# G1Tech-MCP4725-PCB_v02.net
KiCad netlist of a schematic drawn in EAGLE
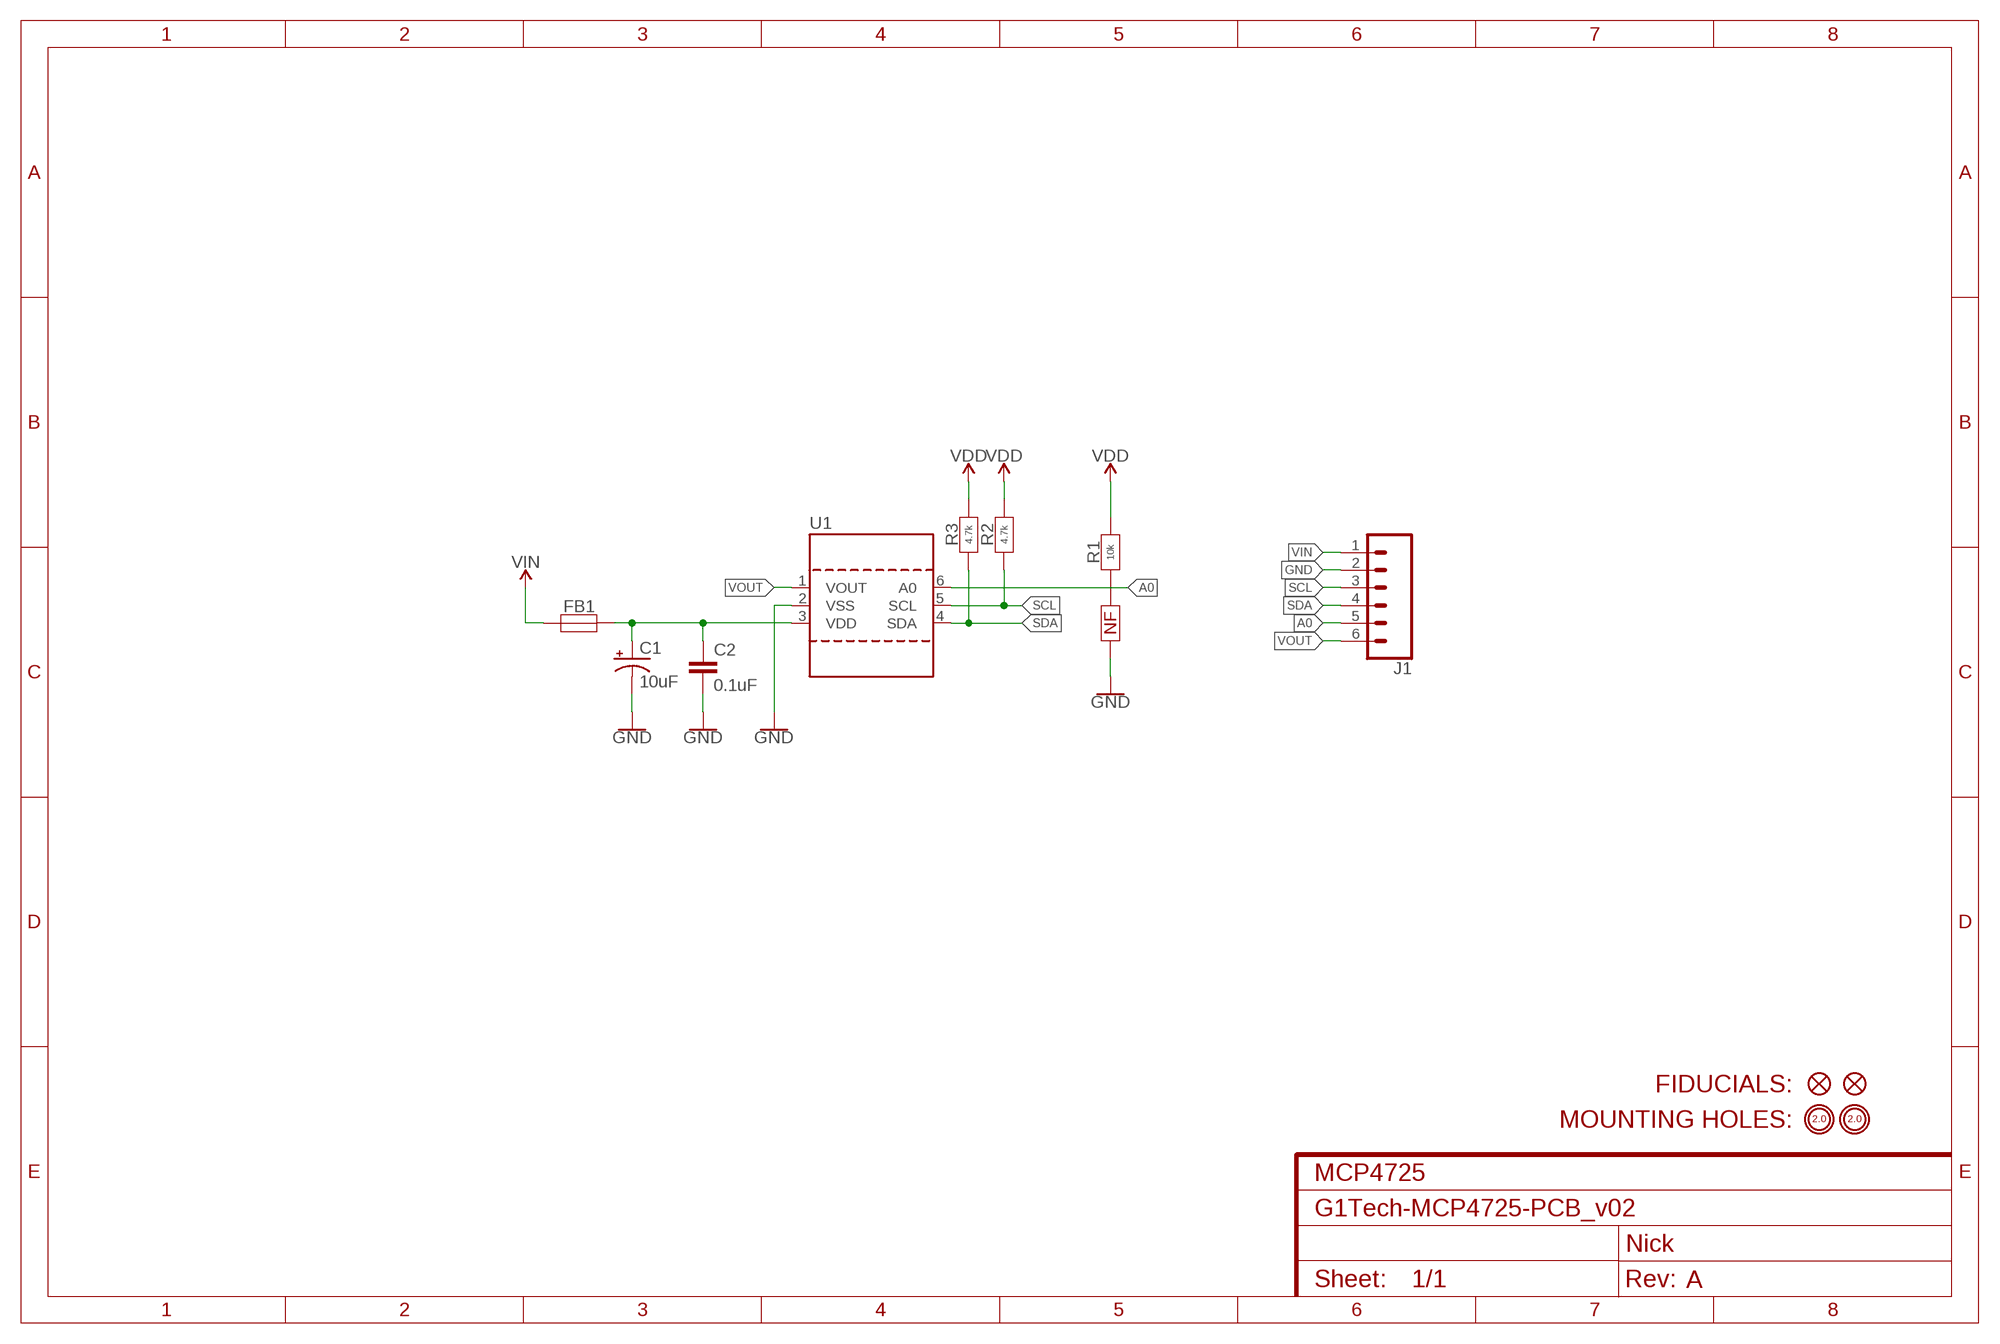
[diagram p0: schematic, sheet 1]

(export (version "E")
  (design (tool "Eeschema 10.0.6"))
  (components
    (comp (ref "C1")
      (value "10uF")
      (footprint "eagle-import:TYPE-A")
      (libsource (lib "eagle-import") (part "C-TYPE-A"))
    )
    (comp (ref "C2")
      (value "0.1uF")
      (footprint "eagle-import:C0603")
      (libsource (lib "eagle-import") (part "C0603"))
    )
    (comp (ref "FB1")
      (value "FERRITE-BEAD-0603")
      (footprint "eagle-import:FB-0603")
      (libsource (lib "eagle-import") (part "FERRITE-BEAD-0603"))
    )
    (comp (ref "FD1")
      (value "FIDUCIAL-1X2")
      (footprint "eagle-import:FIDUCIAL-1X2")
      (libsource (lib "eagle-import") (part "FIDUCIAL-1X2"))
    )
    (comp (ref "FD2")
      (value "FIDUCIAL-1X2")
      (footprint "eagle-import:FIDUCIAL-1X2")
      (libsource (lib "eagle-import") (part "FIDUCIAL-1X2"))
    )
    (comp (ref "H1")
      (value "MOUNTINGHOLE-PLATED-2.0")
      (footprint "eagle-import:MOUNTINGHOLE-PLATED-2.0")
      (libsource (lib "eagle-import") (part "MOUNTINGHOLE-PLATED-2.0"))
    )
    (comp (ref "H2")
      (value "MOUNTINGHOLE-PLATED-2.0")
      (footprint "eagle-import:MOUNTINGHOLE-PLATED-2.0")
      (libsource (lib "eagle-import") (part "MOUNTINGHOLE-PLATED-2.0"))
    )
    (comp (ref "J1")
      (value "CONN-1X6")
      (footprint "eagle-import:1X06_NO_SILK")
      (libsource (lib "eagle-import") (part "CONN-1X6"))
    )
    (comp (ref "R1")
      (value "10k")
      (footprint "eagle-import:YAGEO-JP0603")
      (libsource (lib "eagle-import") (part "JUMPER-0RJP0603-YAGEO"))
    )
    (comp (ref "R2")
      (value "4.7k")
      (footprint "eagle-import:YAGEO-R0603")
      (libsource (lib "eagle-import") (part "YAGEO-R0603"))
    )
    (comp (ref "R3")
      (value "4.7k")
      (footprint "eagle-import:YAGEO-R0603")
      (libsource (lib "eagle-import") (part "YAGEO-R0603"))
    )
    (comp (ref "U1")
      (value "MCP4725")
      (footprint "eagle-import:SOT23-6")
      (libsource (lib "eagle-import") (part "MCP4725"))
    )
  )
  (nets
    (net (code "1") (name "A0") (class "Default")
      (node (ref "J1") (pin "5") (pinfunction "5_5") (pintype "passive"))
      (node (ref "R1") (pin "2") (pinfunction "2_2") (pintype "passive"))
      (node (ref "U1") (pin "6") (pinfunction "A0_6") (pintype "bidirectional"))
    )
    (net (code "2") (name "GND") (class "Default")
      (node (ref "C1") (pin "C") (pinfunction "C_C") (pintype "passive"))
      (node (ref "C2") (pin "2") (pinfunction "2_2") (pintype "passive"))
      (node (ref "J1") (pin "2") (pinfunction "2_2") (pintype "passive"))
      (node (ref "R1") (pin "3") (pinfunction "3_3") (pintype "passive"))
      (node (ref "U1") (pin "2") (pinfunction "VSS_2") (pintype "power_in"))
    )
    (net (code "3") (name "SCL") (class "Default")
      (node (ref "J1") (pin "3") (pinfunction "3_3") (pintype "passive"))
      (node (ref "R2") (pin "1") (pinfunction "1_1") (pintype "passive"))
      (node (ref "U1") (pin "5") (pinfunction "SCL_5") (pintype "bidirectional"))
    )
    (net (code "4") (name "SDA") (class "Default")
      (node (ref "J1") (pin "4") (pinfunction "4_4") (pintype "passive"))
      (node (ref "R3") (pin "1") (pinfunction "1_1") (pintype "passive"))
      (node (ref "U1") (pin "4") (pinfunction "SDA_4") (pintype "bidirectional"))
    )
    (net (code "5") (name "VDD") (class "Default")
      (node (ref "C1") (pin "A") (pinfunction "A_A") (pintype "passive"))
      (node (ref "C2") (pin "1") (pinfunction "1_1") (pintype "passive"))
      (node (ref "FB1") (pin "2") (pinfunction "2_2") (pintype "passive"))
      (node (ref "R1") (pin "1") (pinfunction "1_1") (pintype "passive"))
      (node (ref "R2") (pin "2") (pinfunction "2_2") (pintype "passive"))
      (node (ref "R3") (pin "2") (pinfunction "2_2") (pintype "passive"))
      (node (ref "U1") (pin "3") (pinfunction "VDD_3") (pintype "power_in"))
    )
    (net (code "6") (name "VIN") (class "Default")
      (node (ref "FB1") (pin "1") (pinfunction "1_1") (pintype "passive"))
      (node (ref "J1") (pin "1") (pinfunction "1_1") (pintype "passive"))
    )
    (net (code "7") (name "VOUT") (class "Default")
      (node (ref "J1") (pin "6") (pinfunction "6_6") (pintype "passive"))
      (node (ref "U1") (pin "1") (pinfunction "VOUT_1") (pintype "power_in"))
    )
  )
)
